# M_2_Key_A_E_Card.net
KiCad netlist of a schematic drawn in Altium Designer
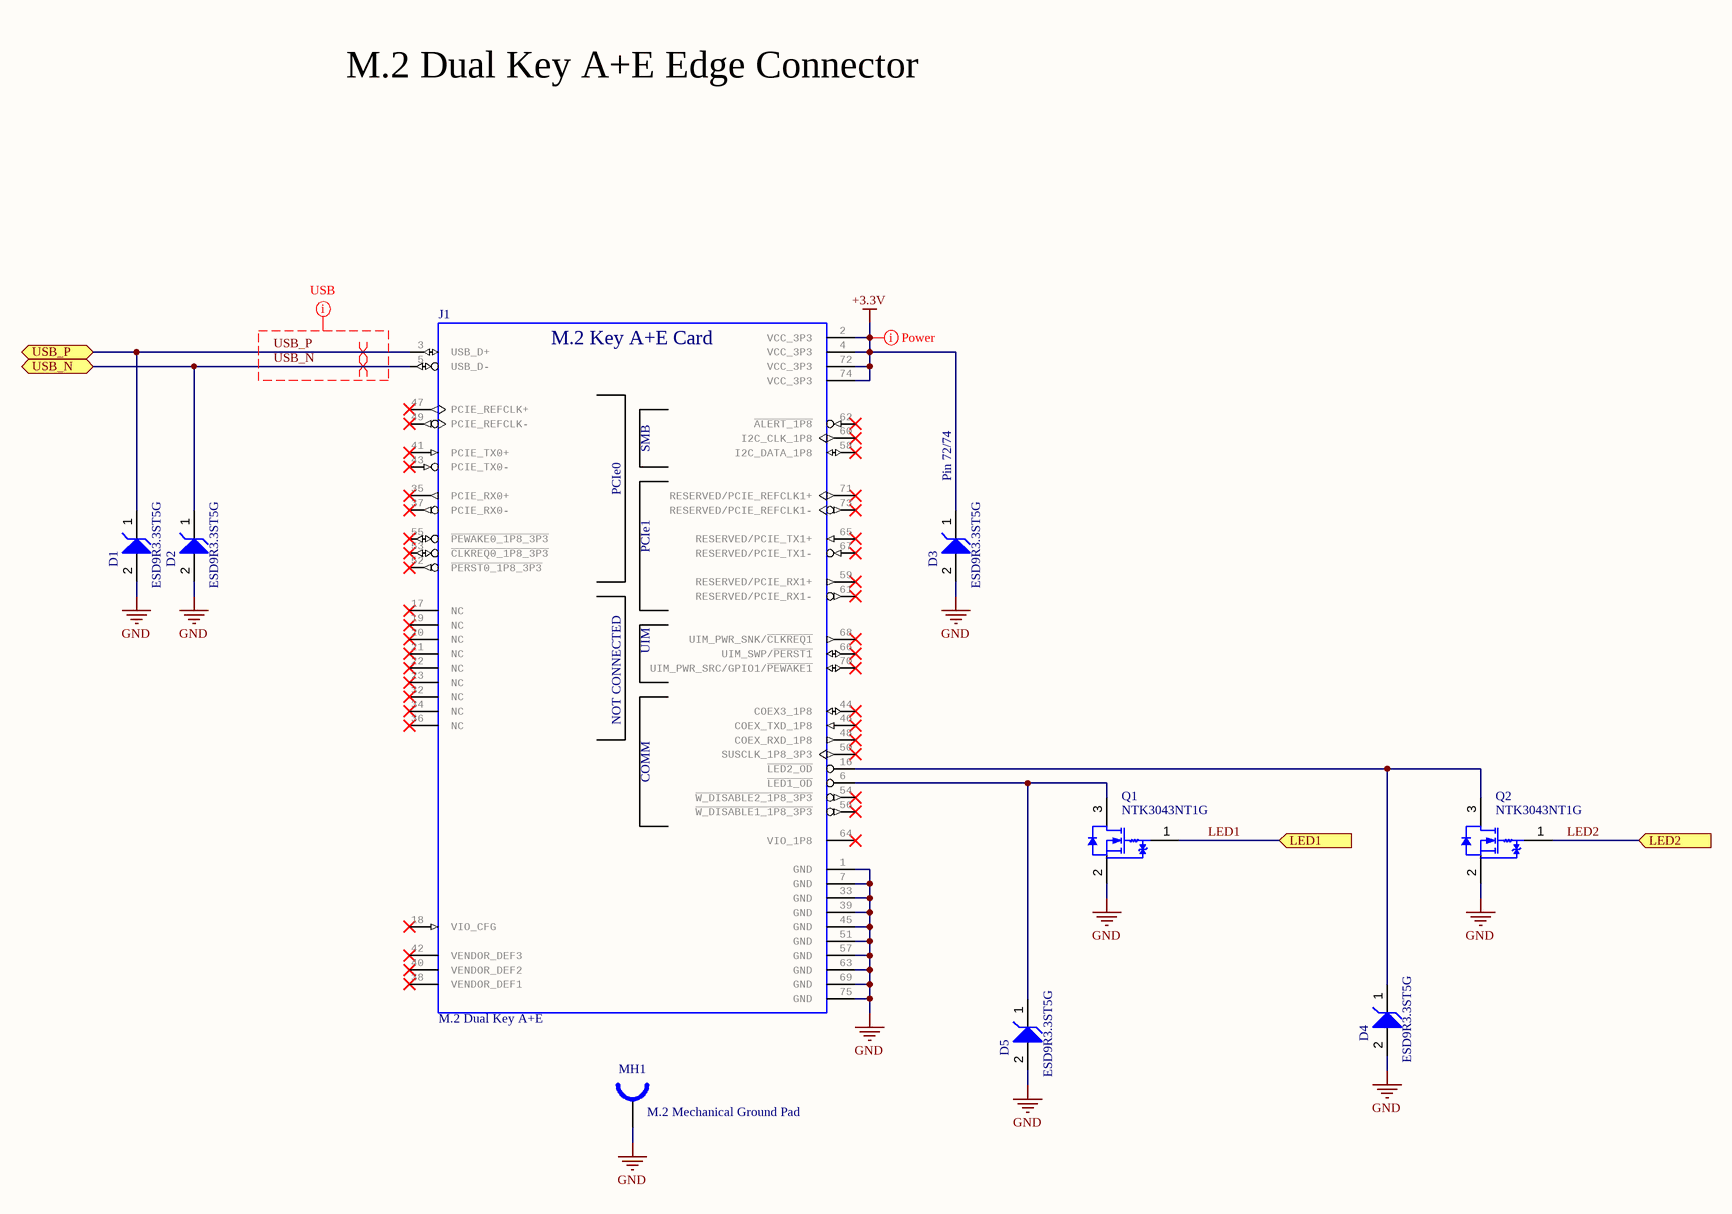
[diagram p0: M.2_Key_A+E_Card.SchDoc]

(export (version "E")
  (design (tool "Eeschema 10.0.6"))
  (components
    (comp (ref "D1")
      (value "ESD9R3.3ST5G")
      (footprint "ONSC-SOD-923-2-514AB-01_V")
      (description "ESD9R3.3S Series 4.8 V 0.5 pF Uni-Directional ESD Protection Diode - SOD-923")
      (libsource (lib "ANavS GmbH") (part "ONSC-K1A2-2_A"))
    )
    (comp (ref "D2")
      (value "ESD9R3.3ST5G")
      (footprint "ONSC-SOD-923-2-514AB-01_V")
      (description "ESD9R3.3S Series 4.8 V 0.5 pF Uni-Directional ESD Protection Diode - SOD-923")
      (libsource (lib "ANavS GmbH") (part "ONSC-K1A2-2_A"))
    )
    (comp (ref "D3")
      (value "ESD9R3.3ST5G")
      (footprint "ONSC-SOD-923-2-514AB-01_V")
      (description "ESD9R3.3S Series 4.8 V 0.5 pF Uni-Directional ESD Protection Diode - SOD-923")
      (libsource (lib "ANavS GmbH") (part "ONSC-K1A2-2_A"))
    )
    (comp (ref "D4")
      (value "ESD9R3.3ST5G")
      (footprint "ONSC-SOD-923-2-514AB-01_V")
      (description "ESD9R3.3S Series 4.8 V 0.5 pF Uni-Directional ESD Protection Diode - SOD-923")
      (libsource (lib "ANavS GmbH") (part "ONSC-K1A2-2_A"))
    )
    (comp (ref "D5")
      (value "ESD9R3.3ST5G")
      (footprint "ONSC-SOD-923-2-514AB-01_V")
      (description "ESD9R3.3S Series 4.8 V 0.5 pF Uni-Directional ESD Protection Diode - SOD-923")
      (libsource (lib "ANavS GmbH") (part "ONSC-K1A2-2_A"))
    )
    (comp (ref "J1")
      (value "M.2 Dual Key A+E")
      (footprint "M.2 Key A+E card-Footprint")
      (description "Golden finger, M.2 Key A+E, Dual, Staggered, Pitch 0.5mm")
      (libsource (lib "ANavS GmbH") (part "M.2_KeyA+E_card-Symbol"))
    )
    (comp (ref "MH1")
      (value "M.2 Mechanical Ground Pad")
      (footprint "M.2 Mechanical Ground Pad Footprint")
      (libsource (lib "ANavS GmbH") (part "Mounting Hole"))
    )
    (comp (ref "Q1")
      (value "NTK3043NT1G")
      (footprint "ONSC-SOT-723-3-631AA-01_V")
      (description "Single N-Channel Small Signal MOSFET with ESD Protection 20V, 285mA, 3.4Ω")
      (libsource (lib "ANavS GmbH") (part "ONSC-NMOS-G1S2D3-3_H"))
    )
    (comp (ref "Q2")
      (value "NTK3043NT1G")
      (footprint "ONSC-SOT-723-3-631AA-01_V")
      (description "Single N-Channel Small Signal MOSFET with ESD Protection 20V, 285mA, 3.4Ω")
      (libsource (lib "ANavS GmbH") (part "ONSC-NMOS-G1S2D3-3_H"))
    )
  )
  (nets
    (net (code "1") (name "+3.3V") (class "Default")
      (node (ref "D3") (pin "1") (pinfunction "K_1") (pintype "passive"))
      (node (ref "J1") (pin "2") (pinfunction "VCC_3P3_2") (pintype "power_in"))
      (node (ref "J1") (pin "4") (pinfunction "VCC_3P3_4") (pintype "power_in"))
      (node (ref "J1") (pin "72") (pinfunction "VCC_3P3_72") (pintype "power_in"))
      (node (ref "J1") (pin "74") (pinfunction "VCC_3P3_74") (pintype "power_in"))
    )
    (net (code "2") (name "/LED1") (class "Default")
      (node (ref "Q1") (pin "1") (pinfunction "G_1") (pintype "passive"))
    )
    (net (code "3") (name "/LED2") (class "Default")
      (node (ref "Q2") (pin "1") (pinfunction "G_1") (pintype "passive"))
    )
    (net (code "4") (name "/USB_N") (class "Default")
      (node (ref "D2") (pin "1") (pinfunction "K_1") (pintype "passive"))
      (node (ref "J1") (pin "5") (pinfunction "USB_D-_5") (pintype "bidirectional"))
    )
    (net (code "5") (name "/USB_P") (class "Default")
      (node (ref "D1") (pin "1") (pinfunction "K_1") (pintype "passive"))
      (node (ref "J1") (pin "3") (pinfunction "USB_D+_3") (pintype "bidirectional"))
    )
    (net (code "6") (name "GND") (class "Default")
      (node (ref "D1") (pin "2") (pinfunction "A_2") (pintype "passive"))
      (node (ref "D2") (pin "2") (pinfunction "A_2") (pintype "passive"))
      (node (ref "D3") (pin "2") (pinfunction "A_2") (pintype "passive"))
      (node (ref "D4") (pin "2") (pinfunction "A_2") (pintype "passive"))
      (node (ref "D5") (pin "2") (pinfunction "A_2") (pintype "passive"))
      (node (ref "J1") (pin "1") (pinfunction "GND_1") (pintype "power_in"))
      (node (ref "J1") (pin "33") (pinfunction "GND_33") (pintype "power_in"))
      (node (ref "J1") (pin "39") (pinfunction "GND_39") (pintype "power_in"))
      (node (ref "J1") (pin "45") (pinfunction "GND_45") (pintype "power_in"))
      (node (ref "J1") (pin "51") (pinfunction "GND_51") (pintype "power_in"))
      (node (ref "J1") (pin "57") (pinfunction "GND_57") (pintype "power_in"))
      (node (ref "J1") (pin "63") (pinfunction "GND_63") (pintype "power_in"))
      (node (ref "J1") (pin "69") (pinfunction "GND_69") (pintype "power_in"))
      (node (ref "J1") (pin "7") (pinfunction "GND_7") (pintype "power_in"))
      (node (ref "J1") (pin "75") (pinfunction "GND_75") (pintype "power_in"))
      (node (ref "MH1") (pin "0") (pinfunction "Chassis_0") (pintype "passive"))
      (node (ref "Q1") (pin "2") (pinfunction "S_2") (pintype "passive"))
      (node (ref "Q2") (pin "2") (pinfunction "S_2") (pintype "passive"))
    )
    (net (code "7") (name "Net-(D4-K)") (class "Default")
      (node (ref "D4") (pin "1") (pinfunction "K_1") (pintype "passive"))
      (node (ref "J1") (pin "16") (pinfunction "LED2_OD_16") (pintype "open_collector"))
      (node (ref "Q2") (pin "3") (pinfunction "D_3") (pintype "passive"))
    )
    (net (code "8") (name "Net-(D5-K)") (class "Default")
      (node (ref "D5") (pin "1") (pinfunction "K_1") (pintype "passive"))
      (node (ref "J1") (pin "6") (pinfunction "LED1_OD_6") (pintype "open_collector"))
      (node (ref "Q1") (pin "3") (pinfunction "D_3") (pintype "passive"))
    )
    (net (code "9") (name "unconnected-(J1-ALERT_1P8-Pad62)") (class "Default")
      (node (ref "J1") (pin "62") (pinfunction "ALERT_1P8_62") (pintype "input+no_connect"))
    )
    (net (code "10") (name "unconnected-(J1-CLKREQ0_1P8_3P3-Pad53)") (class "Default")
      (node (ref "J1") (pin "53") (pinfunction "CLKREQ0_1P8_3P3_53") (pintype "bidirectional+no_connect"))
    )
    (net (code "11") (name "unconnected-(J1-COEX3_1P8-Pad44)") (class "Default")
      (node (ref "J1") (pin "44") (pinfunction "COEX3_1P8_44") (pintype "bidirectional+no_connect"))
    )
    (net (code "12") (name "unconnected-(J1-COEX_RXD_1P8-Pad48)") (class "Default")
      (node (ref "J1") (pin "48") (pinfunction "COEX_RXD_1P8_48") (pintype "output+no_connect"))
    )
    (net (code "13") (name "unconnected-(J1-COEX_TXD_1P8-Pad46)") (class "Default")
      (node (ref "J1") (pin "46") (pinfunction "COEX_TXD_1P8_46") (pintype "input+no_connect"))
    )
    (net (code "14") (name "unconnected-(J1-I2C_CLK_1P8-Pad60)") (class "Default")
      (node (ref "J1") (pin "60") (pinfunction "I2C_CLK_1P8_60") (pintype "output+no_connect"))
    )
    (net (code "15") (name "unconnected-(J1-I2C_DATA_1P8-Pad58)") (class "Default")
      (node (ref "J1") (pin "58") (pinfunction "I2C_DATA_1P8_58") (pintype "bidirectional+no_connect"))
    )
    (net (code "16") (name "unconnected-(J1-NC-Pad17)") (class "Default")
      (node (ref "J1") (pin "17") (pinfunction "NC_17") (pintype "passive+no_connect"))
    )
    (net (code "17") (name "unconnected-(J1-NC-Pad19)") (class "Default")
      (node (ref "J1") (pin "19") (pinfunction "NC_19") (pintype "passive+no_connect"))
    )
    (net (code "18") (name "unconnected-(J1-NC-Pad20)") (class "Default")
      (node (ref "J1") (pin "20") (pinfunction "NC_20") (pintype "passive+no_connect"))
    )
    (net (code "19") (name "unconnected-(J1-NC-Pad21)") (class "Default")
      (node (ref "J1") (pin "21") (pinfunction "NC_21") (pintype "passive+no_connect"))
    )
    (net (code "20") (name "unconnected-(J1-NC-Pad22)") (class "Default")
      (node (ref "J1") (pin "22") (pinfunction "NC_22") (pintype "passive+no_connect"))
    )
    (net (code "21") (name "unconnected-(J1-NC-Pad23)") (class "Default")
      (node (ref "J1") (pin "23") (pinfunction "NC_23") (pintype "passive+no_connect"))
    )
    (net (code "22") (name "unconnected-(J1-NC-Pad32)") (class "Default")
      (node (ref "J1") (pin "32") (pinfunction "NC_32") (pintype "passive+no_connect"))
    )
    (net (code "23") (name "unconnected-(J1-NC-Pad34)") (class "Default")
      (node (ref "J1") (pin "34") (pinfunction "NC_34") (pintype "passive+no_connect"))
    )
    (net (code "24") (name "unconnected-(J1-NC-Pad36)") (class "Default")
      (node (ref "J1") (pin "36") (pinfunction "NC_36") (pintype "passive+no_connect"))
    )
    (net (code "25") (name "unconnected-(J1-PCIE_REFCLK+-Pad47)") (class "Default")
      (node (ref "J1") (pin "47") (pinfunction "PCIE_REFCLK+_47") (pintype "output+no_connect"))
    )
    (net (code "26") (name "unconnected-(J1-PCIE_REFCLK--Pad49)") (class "Default")
      (node (ref "J1") (pin "49") (pinfunction "PCIE_REFCLK-_49") (pintype "output+no_connect"))
    )
    (net (code "27") (name "unconnected-(J1-PCIE_RX0+-Pad35)") (class "Default")
      (node (ref "J1") (pin "35") (pinfunction "PCIE_RX0+_35") (pintype "output+no_connect"))
    )
    (net (code "28") (name "unconnected-(J1-PCIE_RX0--Pad37)") (class "Default")
      (node (ref "J1") (pin "37") (pinfunction "PCIE_RX0-_37") (pintype "output+no_connect"))
    )
    (net (code "29") (name "unconnected-(J1-PCIE_TX0+-Pad41)") (class "Default")
      (node (ref "J1") (pin "41") (pinfunction "PCIE_TX0+_41") (pintype "input+no_connect"))
    )
    (net (code "30") (name "unconnected-(J1-PCIE_TX0--Pad43)") (class "Default")
      (node (ref "J1") (pin "43") (pinfunction "PCIE_TX0-_43") (pintype "input+no_connect"))
    )
    (net (code "31") (name "unconnected-(J1-PERST0_1P8_3P3-Pad52)") (class "Default")
      (node (ref "J1") (pin "52") (pinfunction "PERST0_1P8_3P3_52") (pintype "output+no_connect"))
    )
    (net (code "32") (name "unconnected-(J1-PEWAKE0_1P8_3P3-Pad55)") (class "Default")
      (node (ref "J1") (pin "55") (pinfunction "PEWAKE0_1P8_3P3_55") (pintype "bidirectional+no_connect"))
    )
    (net (code "33") (name "unconnected-(J1-RESERVED{slash}PCIE_REFCLK1+-Pad71)") (class "Default")
      (node (ref "J1") (pin "71") (pinfunction "RESERVED/PCIE_REFCLK1+_71") (pintype "output+no_connect"))
    )
    (net (code "34") (name "unconnected-(J1-RESERVED{slash}PCIE_REFCLK1--Pad73)") (class "Default")
      (node (ref "J1") (pin "73") (pinfunction "RESERVED/PCIE_REFCLK1-_73") (pintype "output+no_connect"))
    )
    (net (code "35") (name "unconnected-(J1-RESERVED{slash}PCIE_RX1+-Pad59)") (class "Default")
      (node (ref "J1") (pin "59") (pinfunction "RESERVED/PCIE_RX1+_59") (pintype "output+no_connect"))
    )
    (net (code "36") (name "unconnected-(J1-RESERVED{slash}PCIE_RX1--Pad61)") (class "Default")
      (node (ref "J1") (pin "61") (pinfunction "RESERVED/PCIE_RX1-_61") (pintype "output+no_connect"))
    )
    (net (code "37") (name "unconnected-(J1-RESERVED{slash}PCIE_TX1+-Pad65)") (class "Default")
      (node (ref "J1") (pin "65") (pinfunction "RESERVED/PCIE_TX1+_65") (pintype "input+no_connect"))
    )
    (net (code "38") (name "unconnected-(J1-RESERVED{slash}PCIE_TX1--Pad67)") (class "Default")
      (node (ref "J1") (pin "67") (pinfunction "RESERVED/PCIE_TX1-_67") (pintype "input+no_connect"))
    )
    (net (code "39") (name "unconnected-(J1-SUSCLK_1P8_3P3-Pad50)") (class "Default")
      (node (ref "J1") (pin "50") (pinfunction "SUSCLK_1P8_3P3_50") (pintype "output+no_connect"))
    )
    (net (code "40") (name "unconnected-(J1-UIM_PWR_SNK{slash}~{CLKREQ1}-Pad68)") (class "Default")
      (node (ref "J1") (pin "68") (pinfunction "UIM_PWR_SNK/~{CLKREQ1}_68") (pintype "output+no_connect"))
    )
    (net (code "41") (name "unconnected-(J1-UIM_PWR_SRC{slash}GPIO1{slash}~{PEWAKE1}-Pad70)") (class "Default")
      (node (ref "J1") (pin "70") (pinfunction "UIM_PWR_SRC/GPIO1/~{PEWAKE1}_70") (pintype "bidirectional+no_connect"))
    )
    (net (code "42") (name "unconnected-(J1-UIM_SWP{slash}~{PERST1}-Pad66)") (class "Default")
      (node (ref "J1") (pin "66") (pinfunction "UIM_SWP/~{PERST1}_66") (pintype "bidirectional+no_connect"))
    )
    (net (code "43") (name "unconnected-(J1-VENDOR_DEF1-Pad38)") (class "Default")
      (node (ref "J1") (pin "38") (pinfunction "VENDOR_DEF1_38") (pintype "passive+no_connect"))
    )
    (net (code "44") (name "unconnected-(J1-VENDOR_DEF2-Pad40)") (class "Default")
      (node (ref "J1") (pin "40") (pinfunction "VENDOR_DEF2_40") (pintype "passive+no_connect"))
    )
    (net (code "45") (name "unconnected-(J1-VENDOR_DEF3-Pad42)") (class "Default")
      (node (ref "J1") (pin "42") (pinfunction "VENDOR_DEF3_42") (pintype "passive+no_connect"))
    )
    (net (code "46") (name "unconnected-(J1-VIO_1P8-Pad64)") (class "Default")
      (node (ref "J1") (pin "64") (pinfunction "VIO_1P8_64") (pintype "power_in+no_connect"))
    )
    (net (code "47") (name "unconnected-(J1-VIO_CFG-Pad18)") (class "Default")
      (node (ref "J1") (pin "18") (pinfunction "VIO_CFG_18") (pintype "input+no_connect"))
    )
    (net (code "48") (name "unconnected-(J1-W_DISABLE1_1P8_3P3-Pad56)") (class "Default")
      (node (ref "J1") (pin "56") (pinfunction "W_DISABLE1_1P8_3P3_56") (pintype "output+no_connect"))
    )
    (net (code "49") (name "unconnected-(J1-W_DISABLE2_1P8_3P3-Pad54)") (class "Default")
      (node (ref "J1") (pin "54") (pinfunction "W_DISABLE2_1P8_3P3_54") (pintype "output+no_connect"))
    )
  )
)
